# CATS-FAT-CAN.net
KiCad netlist of a schematic drawn in Altium Designer
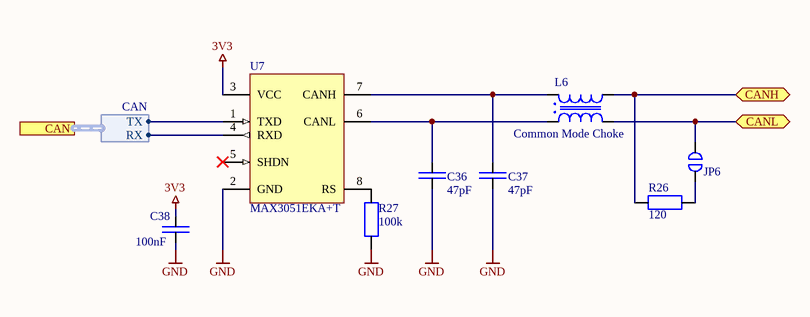
[diagram p0: CATS-FAT-CAN.SchDoc]

(export (version "E")
  (design (tool "Eeschema 10.0.6"))
  (components
    (comp (ref "C36")
      (value "47pF")
      (footprint "SMD Keramikkondensator 0603")
      (description "SMD Ceramic Capacitor E6")
      (libsource (lib "Ceramic Capacitors-E6") (part "E6 - 47pF"))
    )
    (comp (ref "C37")
      (value "47pF")
      (footprint "SMD Keramikkondensator 0603")
      (description "SMD Ceramic Capacitor E6")
      (libsource (lib "Ceramic Capacitors-E6") (part "E6 - 47pF"))
    )
    (comp (ref "C38")
      (value "100nF")
      (footprint "SMD Keramikkondensator 0603")
      (description "SMD Ceramic Capacitor E6")
      (libsource (lib "Ceramic Capacitors-E6") (part "E6 - 100nF"))
    )
    (comp (ref "JP6")
      (value "Jumper")
      (footprint "SMD Solder Jumper 1x2mm")
      (description "Single Position Jumper")
      (libsource (lib "Connectors") (part "Jumper-1"))
    )
    (comp (ref "L6")
      (value "Common Mode Choke")
      (footprint "SMD Common Mode Choke 2x1.2")
      (description "2 Line Common Mode Choke Surface Mount 370mA DCR 300mOhm")
      (libsource (lib "Inductors") (part "Common Mode Choke (CAN)"))
    )
    (comp (ref "R26")
      (value "120")
      (footprint "SMD Widerstand 0603")
      (description "SMD Chip Resistor E24")
      (libsource (lib "Resistors-E24") (part "E24 - 120"))
    )
    (comp (ref "R27")
      (value "100k")
      (footprint "SMD Widerstand 0603")
      (description "SMD Chip Resistor E24")
      (libsource (lib "Resistors-E24") (part "E24 - 100k"))
    )
    (comp (ref "U7")
      (value "MAX3051EKA+T")
      (footprint "SMD IC SOT-23-8")
      (description "+3.3V, 1Mbps, Low-Supply-Current\r\nCAN Transceiver")
      (libsource (lib "Communication") (part "MAX3051EKA+T"))
    )
  )
  (nets
    (net (code "2") (name "/CANH") (class "Default")
      (node (ref "L6") (pin "2") (pinfunction "2_2") (pintype "passive"))
      (node (ref "R26") (pin "1") (pinfunction "1_1") (pintype "passive"))
    )
    (net (code "3") (name "/CANL") (class "Default")
      (node (ref "JP6") (pin "1") (pintype "passive"))
      (node (ref "L6") (pin "3") (pinfunction "3_3") (pintype "passive"))
    )
    (net (code "4") (name "/RX") (class "Default")
      (node (ref "U7") (pin "4") (pinfunction "RXD_4") (pintype "output"))
    )
    (net (code "5") (name "/TX") (class "Default")
      (node (ref "U7") (pin "1") (pinfunction "TXD_1") (pintype "input"))
    )
    (net (code "7") (name "3V3") (class "Default")
      (node (ref "C38") (pin "2") (pinfunction "2_2") (pintype "passive"))
      (node (ref "U7") (pin "3") (pinfunction "VCC_3") (pintype "passive"))
    )
    (net (code "8") (name "GND") (class "Default")
      (node (ref "C36") (pin "1") (pinfunction "1_1") (pintype "passive"))
      (node (ref "C37") (pin "1") (pinfunction "1_1") (pintype "passive"))
      (node (ref "C38") (pin "1") (pinfunction "1_1") (pintype "passive"))
      (node (ref "R27") (pin "1") (pinfunction "1_1") (pintype "passive"))
      (node (ref "U7") (pin "2") (pinfunction "GND_2") (pintype "passive"))
    )
    (net (code "9") (name "Net-(JP6-Pad2)") (class "Default")
      (node (ref "JP6") (pin "2") (pintype "passive"))
      (node (ref "R26") (pin "2") (pinfunction "2_2") (pintype "passive"))
    )
    (net (code "10") (name "Net-(U7-CANH)") (class "Default")
      (node (ref "C37") (pin "2") (pinfunction "2_2") (pintype "passive"))
      (node (ref "L6") (pin "1") (pinfunction "1_1") (pintype "passive"))
      (node (ref "U7") (pin "7") (pinfunction "CANH_7") (pintype "passive"))
    )
    (net (code "11") (name "Net-(U7-CANL)") (class "Default")
      (node (ref "C36") (pin "2") (pinfunction "2_2") (pintype "passive"))
      (node (ref "L6") (pin "4") (pinfunction "4_4") (pintype "passive"))
      (node (ref "U7") (pin "6") (pinfunction "CANL_6") (pintype "passive"))
    )
    (net (code "12") (name "Net-(U7-RS)") (class "Default")
      (node (ref "R27") (pin "2") (pinfunction "2_2") (pintype "passive"))
      (node (ref "U7") (pin "8") (pinfunction "RS_8") (pintype "passive"))
    )
    (net (code "13") (name "unconnected-(U7-SHDN-Pad5)") (class "Default")
      (node (ref "U7") (pin "5") (pinfunction "SHDN_5") (pintype "input+no_connect"))
    )
  )
)
